# Optical_RX_TX.net
KiCad netlist of a schematic drawn in Altium Designer
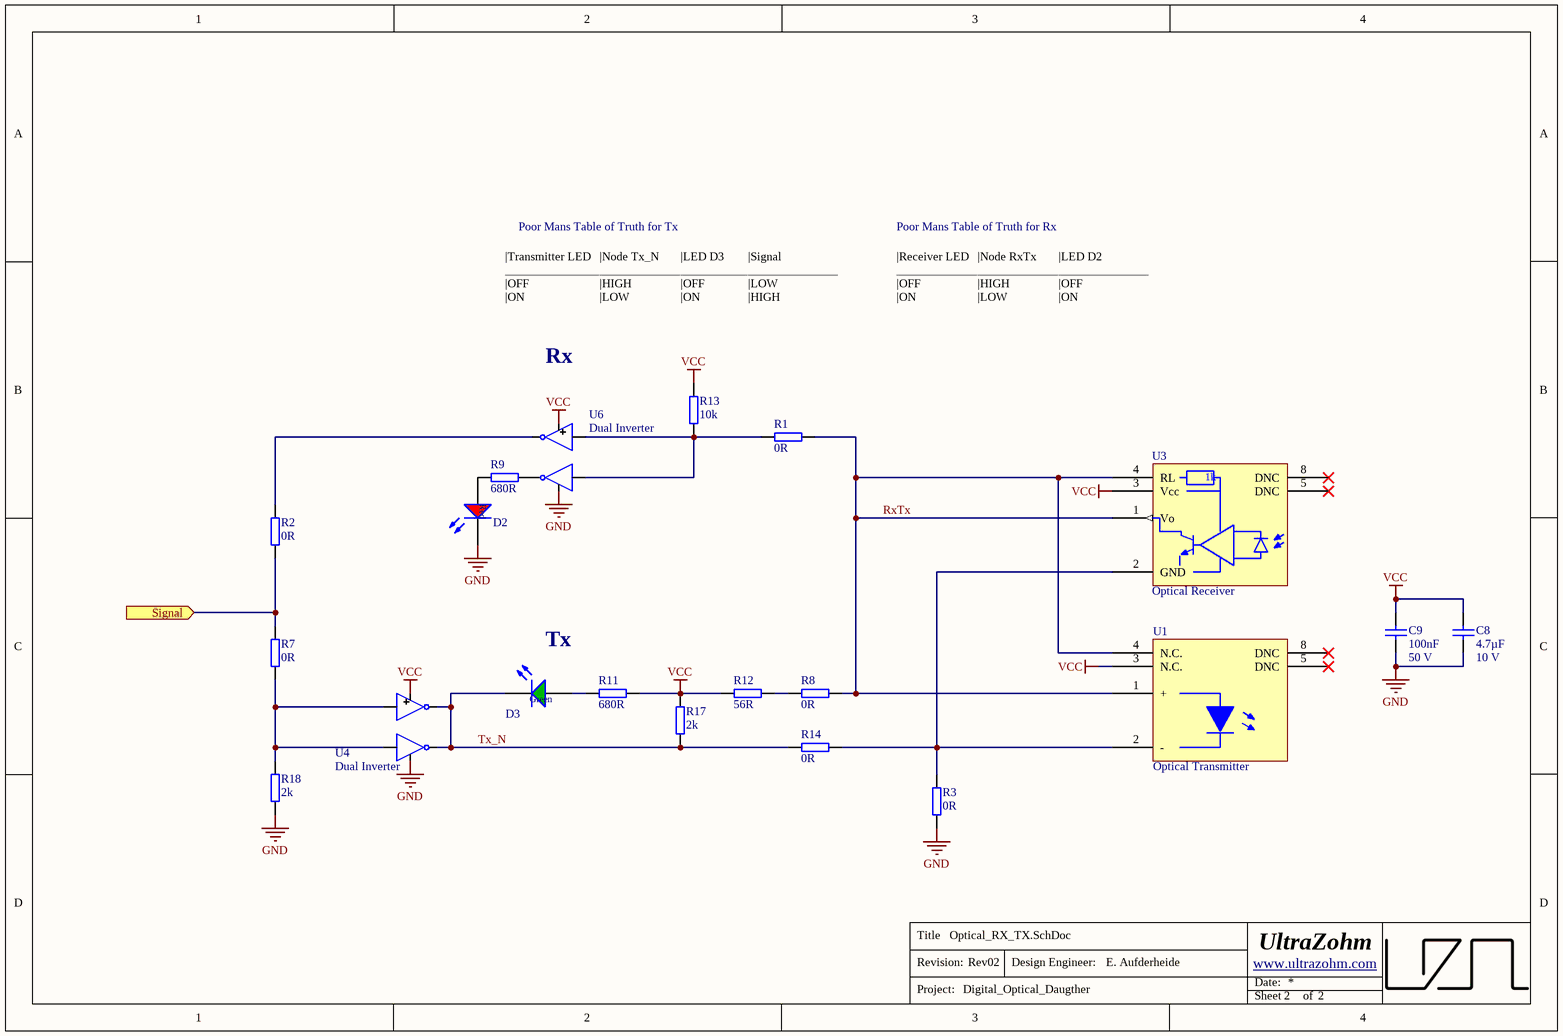
[diagram p0: Optical_RX_TX.SchDoc]

(export (version "E")
  (design (tool "Eeschema 10.0.6"))
  (components
    (comp (ref "C8")
      (value "4.7µF")
      (footprint "CAP_2012X06N")
      (description "CAP 0805 (2012 Metric) SMD")
      (fields
        (field (name "TOLERANCE") "±10%")
        (field (name "MF") "Taiyo Yuden")
        (field (name "VOLTAGE") "10 V")
        (field (name "CREATED") "2018_09_06_AGeiger")
      )
      (libsource (lib "UZOhm_Optical") (part "C_0805"))
    )
    (comp (ref "C9")
      (value "100nF")
      (footprint "C_0603(1608)100_L")
      (description "CAP 0603 (1608 Metric) SMD")
      (fields
        (field (name "TOLERANCE") "±5%")
        (field (name "RATED VOLTAGE") "50 V")
        (field (name "LCSC PART NUMBER") "C14663")
        (field (name "CREATED") "2018_09_06_AGeiger")
      )
      (libsource (lib "UZOhm_Optical") (part "C_0603"))
    )
    (comp (ref "D2")
      (value "150060RS75000")
      (footprint "WL-SMCW_0603")
      (description "WL-SMCW SMD Mono-color Chip LED Waterclear, size 0603, Red, 2 V, 140°")
      (fields
        (field (name "MF") "Wuerth Elektronik")
        (field (name "LCSC PART NUMBER") "C2286")
        (field (name "CREATED") "2018_09_06_AGeiger")
      )
      (libsource (lib "UZOhm_Optical") (part "LED_Red_0603"))
    )
    (comp (ref "D3")
      (value "150060GS75000")
      (footprint "WL-SMCW_0603")
      (description "WL-SMCW SMD Mono-color Chip LED Waterclear, size 0603, Green, 3.2 V, 140°")
      (fields
        (field (name "MF") "Wuerth Elektronik")
        (field (name "LCSC PART NUMBER") "C965804")
        (field (name "CREATED") "2018_09_06_AGeiger")
      )
      (libsource (lib "UZOhm_Optical") (part "LED_Green_0603"))
    )
    (comp (ref "R1")
      (value "0R")
      (footprint "R_0603_N")
      (description "SMD Resistor 0603")
      (fields
        (field (name "TOLERANCE") "1%")
        (field (name "VOLTAGE") "75V")
        (field (name "CREATED") "2018_09_06_AGeiger")
      )
      (libsource (lib "UZOhm_Optical") (part "R_0603_JLC"))
    )
    (comp (ref "R2")
      (value "0R")
      (footprint "R_0603_N")
      (description "SMD Resistor 0603")
      (fields
        (field (name "TOLERANCE") "1%")
        (field (name "VOLTAGE") "75V")
        (field (name "CREATED") "2018_09_06_AGeiger")
      )
      (libsource (lib "UZOhm_Optical") (part "R_0603_JLC"))
    )
    (comp (ref "R3")
      (value "0R")
      (footprint "R_0603_N")
      (description "SMD Resistor 0603")
      (fields
        (field (name "TOLERANCE") "1%")
        (field (name "VOLTAGE") "75V")
        (field (name "CREATED") "2018_09_06_AGeiger")
      )
      (libsource (lib "UZOhm_Optical") (part "R_0603"))
    )
    (comp (ref "R7")
      (value "0R")
      (footprint "R_0603_N")
      (description "SMD Resistor 0603")
      (fields
        (field (name "TOLERANCE") "1%")
        (field (name "VOLTAGE") "75V")
        (field (name "CREATED") "2018_09_06_AGeiger")
      )
      (libsource (lib "UZOhm_Optical") (part "R_0603_JLC"))
    )
    (comp (ref "R8")
      (value "0R")
      (footprint "R_0603_N")
      (description "SMD Resistor 0603")
      (fields
        (field (name "TOLERANCE") "1%")
        (field (name "VOLTAGE") "75V")
        (field (name "CREATED") "2018_09_06_AGeiger")
      )
      (libsource (lib "UZOhm_Optical") (part "R_0603_JLC"))
    )
    (comp (ref "R9")
      (value "680R")
      (footprint "R_0603_N")
      (description "SMD Resistor 0603")
      (fields
        (field (name "TOLERANCE") "1%")
        (field (name "VOLTAGE") "75V")
        (field (name "CREATED") "2018_09_06_AGeiger")
      )
      (libsource (lib "UZOhm_Optical") (part "R_0603"))
    )
    (comp (ref "R11")
      (value "680R")
      (footprint "R_0603_N")
      (description "SMD Resistor 0603")
      (fields
        (field (name "TOLERANCE") "1%")
        (field (name "VOLTAGE") "75V")
        (field (name "CREATED") "2018_09_06_AGeiger")
      )
      (libsource (lib "UZOhm_Optical") (part "R_0603"))
    )
    (comp (ref "R12")
      (value "56R")
      (footprint "RES_2012X06N")
      (description "SMD Resistor 0805")
      (fields (field (name "MF") "Bourns") (field (name "MPN") "CR0805-FX-1200ELF"))
      (libsource (lib "UZOhm_Optical") (part "R_0805"))
    )
    (comp (ref "R13")
      (value "10k")
      (footprint "R_0603_TE")
      (description "Generic resistor")
      (fields
        (field (name "MANUFACTURER PART NUMBER") "UZgen_R_0603_10k")
        (field (name "MANUFACTURER") "UZgen")
        (field (name "CREATED FROM") "AGeiger")
      )
      (libsource (lib "user") (part "RES"))
    )
    (comp (ref "R14")
      (value "0R")
      (footprint "R_0603_N")
      (description "SMD Resistor 0603")
      (fields
        (field (name "TOLERANCE") "1%")
        (field (name "VOLTAGE") "75V")
        (field (name "CREATED") "2018_09_06_AGeiger")
      )
      (libsource (lib "UZOhm_Optical") (part "R_0603_JLC"))
    )
    (comp (ref "R17")
      (value "2k")
      (footprint "R_0603_N")
      (description "SMD Resistor 0603")
      (fields
        (field (name "TOLERANCE") "1%")
        (field (name "VOLTAGE") "75 V")
        (field (name "CREATED") "2018_09_06_AGeiger")
      )
      (libsource (lib "UZOhm_Optical") (part "R_0603"))
    )
    (comp (ref "R18")
      (value "2k")
      (footprint "R_0603_N")
      (description "SMD Resistor 0603")
      (fields
        (field (name "TOLERANCE") "1%")
        (field (name "VOLTAGE") "75 V")
        (field (name "CREATED") "2018_09_06_AGeiger")
      )
      (libsource (lib "UZOhm_Optical") (part "R_0603"))
    )
    (comp (ref "U1")
      (value "Optical Transmitter")
      (footprint "HFBRx5XX")
      (description "Fibre Optic Transmitters, Link Horiz 5MBd Tx RoHS")
      (fields
        (field (name "MF") "Broadcom/Avago")
        (field (name "MPN") "HFBR-1521Z")
        (field (name "CREATED") "2019_04_09_Kreppel")
      )
      (libsource (lib "UZOhm_Optical") (part "HFBR-1521Z"))
    )
    (comp (ref "U3")
      (value "Optical Receiver")
      (footprint "HFBRx5XX")
      (description "Fibre Optic Receivers, LINK HORIZ 5MBd RC VR RoHS")
      (fields
        (field (name "MF") "Boadcom/Avago")
        (field (name "MPN") "HFBR-2521Z")
        (field (name "CREATED") "2019_04_09_Kreppel")
      )
      (libsource (lib "UZOhm_Optical") (part "HFBR-2528Z"))
    )
    (comp (ref "U4")
      (value "Dual Inverter")
      (footprint "SN74LVC2GU04DCKR")
      (description "This dual inverter is designed for 1.65-V to 5.5-V VCC\r\noperation.")
      (fields (field (name "LCSC PART NUMBER") "C116660"))
      (libsource (lib "UZOhm_Optical") (part "SN74LVC2GU04DCKR"))
    )
    (comp (ref "U6")
      (value "Dual Inverter")
      (footprint "SN74LVC2GU04DCKR")
      (description "This dual inverter is designed for 1.65-V to 5.5-V VCC\r\noperation.")
      (fields (field (name "LCSC PART NUMBER") "C116660"))
      (libsource (lib "UZOhm_Optical") (part "SN74LVC2GU04DCKR"))
    )
  )
  (nets
    (net (code "1") (name "/RxTx") (class "Default")
      (node (ref "R1") (pin "2") (pinfunction "2_2") (pintype "passive"))
      (node (ref "R8") (pin "2") (pinfunction "2_2") (pintype "passive"))
      (node (ref "U1") (pin "1") (pinfunction "+_1") (pintype "passive"))
      (node (ref "U1") (pin "4") (pinfunction "N.C._4") (pintype "passive"))
      (node (ref "U3") (pin "1") (pinfunction "Vo_1") (pintype "output"))
      (node (ref "U3") (pin "4") (pinfunction "RL_4") (pintype "passive"))
    )
    (net (code "2") (name "/Signal") (class "Default")
      (node (ref "R2") (pin "1") (pinfunction "1_1") (pintype "passive"))
      (node (ref "R7") (pin "2") (pinfunction "2_2") (pintype "passive"))
    )
    (net (code "3") (name "/Tx_N") (class "Default")
      (node (ref "D3") (pin "1") (pinfunction "K_1") (pintype "passive"))
      (node (ref "R14") (pin "1") (pinfunction "1_1") (pintype "passive"))
      (node (ref "R17") (pin "1") (pinfunction "1_1") (pintype "passive"))
      (node (ref "U4") (pin "4") (pinfunction "OUT2_4") (pintype "passive"))
      (node (ref "U4") (pin "6") (pinfunction "OUT2_6") (pintype "passive"))
    )
    (net (code "4") (name "GND") (class "Default")
      (node (ref "C8") (pin "2") (pinfunction "2_2") (pintype "passive"))
      (node (ref "C9") (pin "2") (pinfunction "2_2") (pintype "passive"))
      (node (ref "D2") (pin "1") (pinfunction "K_1") (pintype "passive"))
      (node (ref "R18") (pin "1") (pinfunction "1_1") (pintype "passive"))
      (node (ref "R3") (pin "2") (pinfunction "2_2") (pintype "passive"))
      (node (ref "U4") (pin "2") (pinfunction "GND_2") (pintype "passive"))
      (node (ref "U6") (pin "2") (pinfunction "GND_2") (pintype "passive"))
    )
    (net (code "5") (name "Net-(D2-A)") (class "Default")
      (node (ref "D2") (pin "2") (pinfunction "A_2") (pintype "passive"))
      (node (ref "R9") (pin "2") (pinfunction "2_2") (pintype "passive"))
    )
    (net (code "6") (name "Net-(D3-A)") (class "Default")
      (node (ref "D3") (pin "2") (pinfunction "A_2") (pintype "passive"))
      (node (ref "R11") (pin "2") (pinfunction "2_2") (pintype "passive"))
    )
    (net (code "7") (name "Net-(R2-Pad2)") (class "Default")
      (node (ref "R2") (pin "2") (pinfunction "2_2") (pintype "passive"))
      (node (ref "U6") (pin "6") (pinfunction "OUT2_6") (pintype "passive"))
    )
    (net (code "8") (name "Net-(R9-Pad1)") (class "Default")
      (node (ref "R9") (pin "1") (pinfunction "1_1") (pintype "passive"))
      (node (ref "U6") (pin "4") (pinfunction "OUT2_4") (pintype "passive"))
    )
    (net (code "9") (name "Net-(R12-Pad2)") (class "Default")
      (node (ref "R12") (pin "2") (pintype "passive"))
      (node (ref "R8") (pin "1") (pinfunction "1_1") (pintype "passive"))
    )
    (net (code "10") (name "Net-(U1--)") (class "Default")
      (node (ref "R14") (pin "2") (pinfunction "2_2") (pintype "passive"))
      (node (ref "R3") (pin "1") (pinfunction "1_1") (pintype "passive"))
      (node (ref "U1") (pin "2") (pinfunction "-_2") (pintype "passive"))
      (node (ref "U3") (pin "2") (pinfunction "GND_2") (pintype "power_in"))
    )
    (net (code "11") (name "Net-(U4-IN1)") (class "Default")
      (node (ref "R18") (pin "2") (pinfunction "2_2") (pintype "passive"))
      (node (ref "R7") (pin "1") (pinfunction "1_1") (pintype "passive"))
      (node (ref "U4") (pin "1") (pinfunction "IN1_1") (pintype "passive"))
      (node (ref "U4") (pin "3") (pinfunction "IN2_3") (pintype "passive"))
    )
    (net (code "12") (name "Net-(U6-IN1)") (class "Default")
      (node (ref "R1") (pin "1") (pinfunction "1_1") (pintype "passive"))
      (node (ref "R13") (pin "1") (pinfunction "1_1") (pintype "passive"))
      (node (ref "U6") (pin "1") (pinfunction "IN1_1") (pintype "passive"))
      (node (ref "U6") (pin "3") (pinfunction "IN2_3") (pintype "passive"))
    )
    (net (code "13") (name "VCC") (class "Default")
      (node (ref "C8") (pin "1") (pinfunction "1_1") (pintype "passive"))
      (node (ref "C9") (pin "1") (pinfunction "1_1") (pintype "passive"))
      (node (ref "R11") (pin "1") (pinfunction "1_1") (pintype "passive"))
      (node (ref "R12") (pin "1") (pintype "passive"))
      (node (ref "R13") (pin "2") (pinfunction "2_2") (pintype "passive"))
      (node (ref "R17") (pin "2") (pinfunction "2_2") (pintype "passive"))
      (node (ref "U1") (pin "3") (pinfunction "N.C._3") (pintype "passive"))
      (node (ref "U3") (pin "3") (pinfunction "Vcc_3") (pintype "power_in"))
      (node (ref "U4") (pin "5") (pinfunction "VCC_5") (pintype "passive"))
      (node (ref "U6") (pin "5") (pinfunction "VCC_5") (pintype "passive"))
    )
    (net (code "14") (name "unconnected-(U1-DNC-Pad5)") (class "Default")
      (node (ref "U1") (pin "5") (pinfunction "DNC_5") (pintype "passive+no_connect"))
    )
    (net (code "15") (name "unconnected-(U1-DNC-Pad8)") (class "Default")
      (node (ref "U1") (pin "8") (pinfunction "DNC_8") (pintype "passive+no_connect"))
    )
    (net (code "16") (name "unconnected-(U3-DNC-Pad5)") (class "Default")
      (node (ref "U3") (pin "5") (pinfunction "DNC_5") (pintype "passive+no_connect"))
    )
    (net (code "17") (name "unconnected-(U3-DNC-Pad8)") (class "Default")
      (node (ref "U3") (pin "8") (pinfunction "DNC_8") (pintype "passive+no_connect"))
    )
  )
)
